# UI_Controller_Damping_R.net
KiCad netlist of a schematic drawn in EAGLE
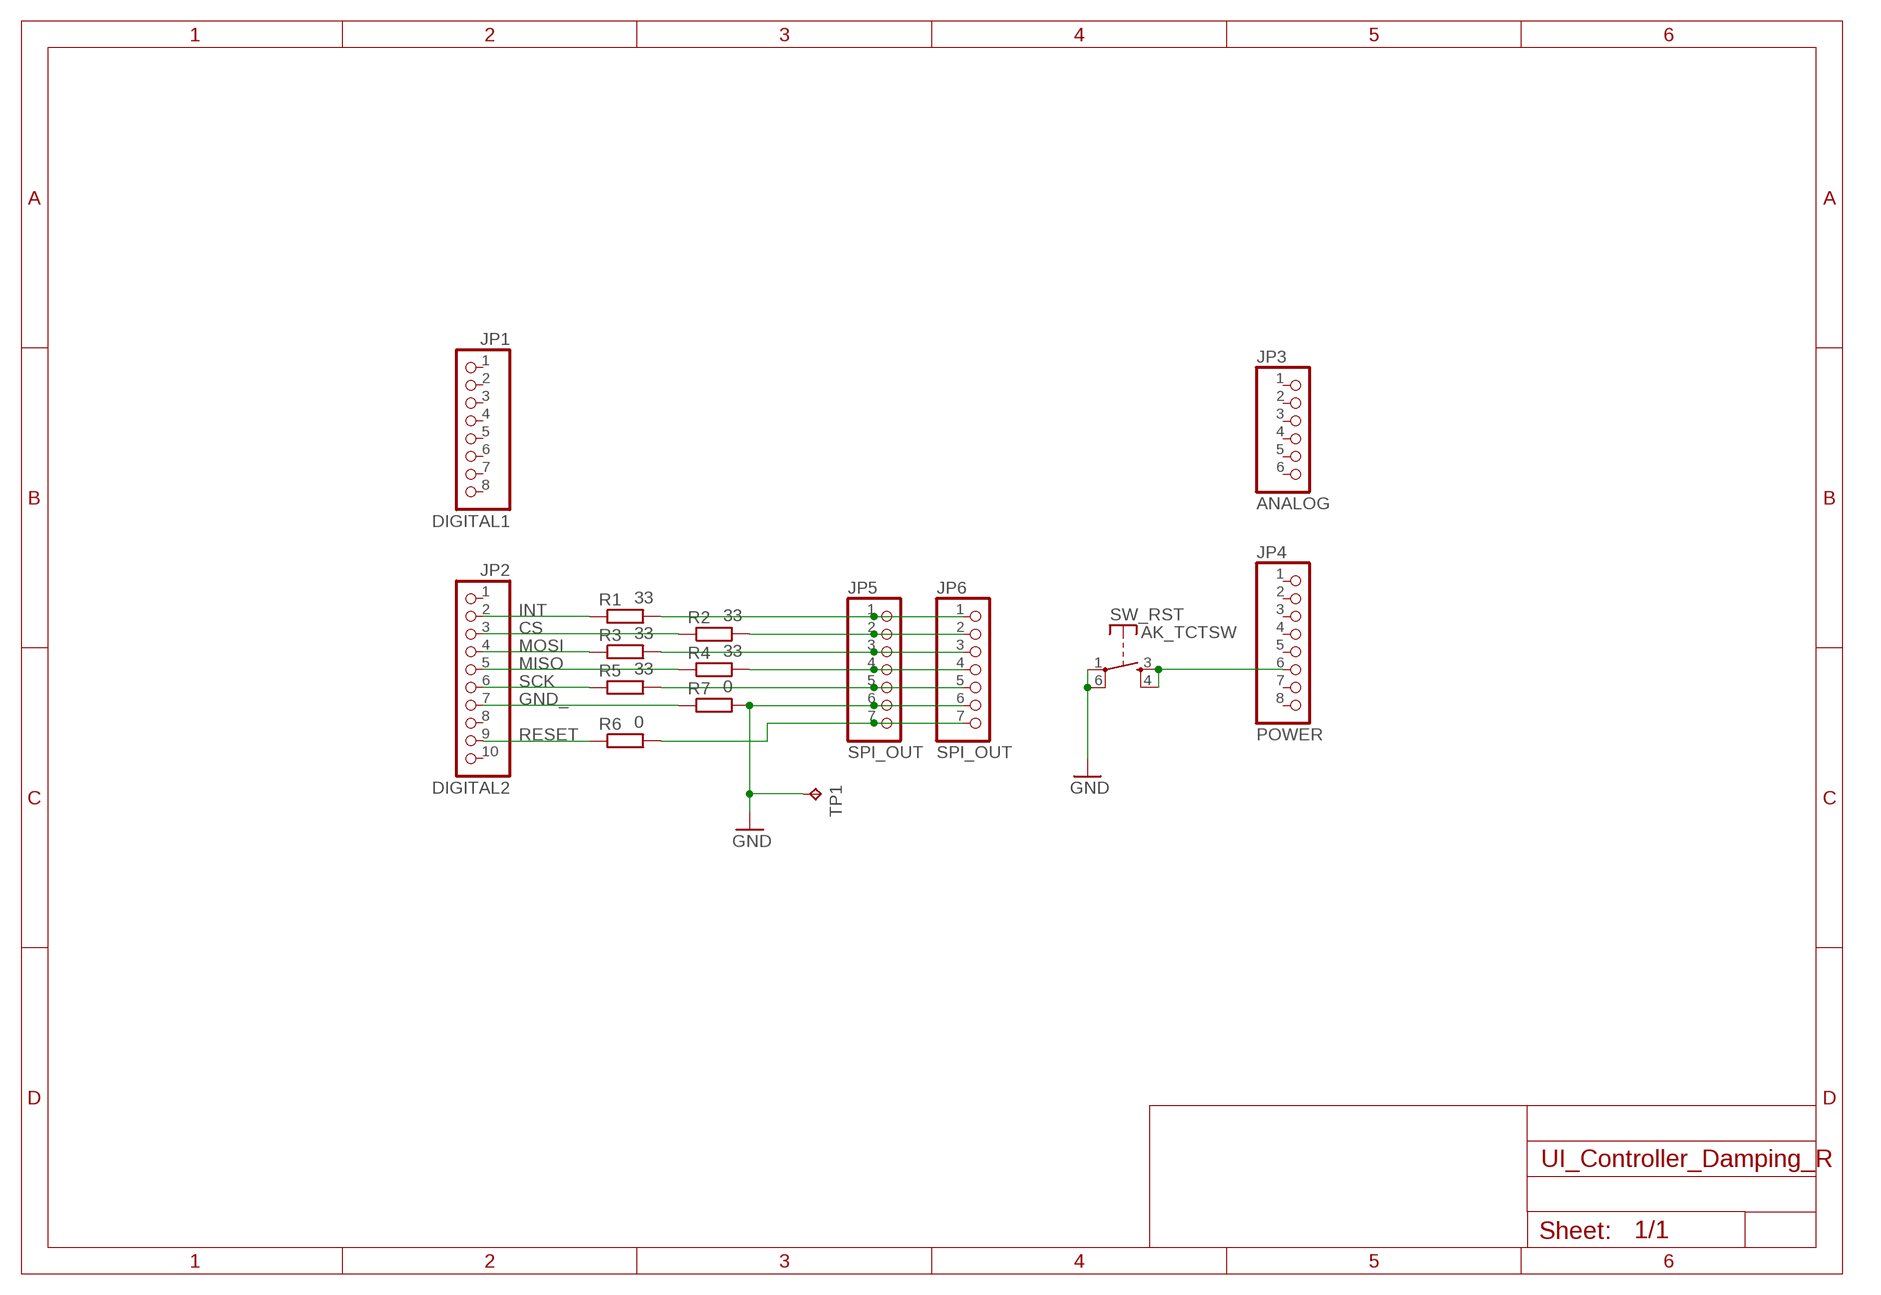
[diagram p0: schematic, sheet 1]

(export (version "E")
  (design (tool "Eeschema 10.0.6"))
  (components
    (comp (ref "JP1")
      (value "DIGITAL1")
      (footprint "eagle-import:1X08")
      (libsource (lib "eagle-import") (part "PINHD-1X8"))
    )
    (comp (ref "JP2")
      (value "DIGITAL2")
      (footprint "eagle-import:1X10")
      (libsource (lib "eagle-import") (part "PINHD-1X10"))
    )
    (comp (ref "JP3")
      (value "ANALOG")
      (footprint "eagle-import:1X06")
      (libsource (lib "eagle-import") (part "PINHD-1X6"))
    )
    (comp (ref "JP4")
      (value "POWER")
      (footprint "eagle-import:1X08")
      (libsource (lib "eagle-import") (part "PINHD-1X8"))
    )
    (comp (ref "JP5")
      (value "SPI_OUT")
      (footprint "eagle-import:1X07")
      (libsource (lib "eagle-import") (part "PINHD-1X7"))
    )
    (comp (ref "JP6")
      (value "SPI_OUT")
      (footprint "eagle-import:1X07")
      (libsource (lib "eagle-import") (part "PINHD-1X7"))
    )
    (comp (ref "R1")
      (value "33")
      (footprint "eagle-import:0207_7")
      (libsource (lib "eagle-import") (part "R-EU_0207/7"))
    )
    (comp (ref "R2")
      (value "33")
      (footprint "eagle-import:0207_7")
      (libsource (lib "eagle-import") (part "R-EU_0207/7"))
    )
    (comp (ref "R3")
      (value "33")
      (footprint "eagle-import:0207_7")
      (libsource (lib "eagle-import") (part "R-EU_0207/7"))
    )
    (comp (ref "R4")
      (value "33")
      (footprint "eagle-import:0207_7")
      (libsource (lib "eagle-import") (part "R-EU_0207/7"))
    )
    (comp (ref "R5")
      (value "33")
      (footprint "eagle-import:0207_7")
      (libsource (lib "eagle-import") (part "R-EU_0207/7"))
    )
    (comp (ref "R6")
      (value "0")
      (footprint "eagle-import:0207_7")
      (libsource (lib "eagle-import") (part "R-EU_0207/7"))
    )
    (comp (ref "R7")
      (value "0")
      (footprint "eagle-import:0207_7")
      (libsource (lib "eagle-import") (part "R-EU_0207/7"))
    )
    (comp (ref "SW_RST")
      (value "AK_TCTSW")
      (footprint "eagle-import:TME1")
      (libsource (lib "eagle-import") (part "AK_TCTSW"))
    )
    (comp (ref "TP1")
      (value "TPPAD1-13")
      (footprint "eagle-import:P1-13")
      (libsource (lib "eagle-import") (part "TPPAD1-13"))
    )
  )
  (nets
    (net (code "1") (name "/CS") (class "Default")
      (node (ref "JP2") (pin "3") (pinfunction "3_3") (pintype "passive"))
      (node (ref "R2") (pin "1") (pinfunction "1_1") (pintype "passive"))
    )
    (net (code "2") (name "/GND_") (class "Default")
      (node (ref "JP2") (pin "7") (pinfunction "7_7") (pintype "passive"))
      (node (ref "R7") (pin "1") (pinfunction "1_1") (pintype "passive"))
    )
    (net (code "3") (name "/INT") (class "Default")
      (node (ref "JP2") (pin "2") (pinfunction "2_2") (pintype "passive"))
      (node (ref "R1") (pin "1") (pinfunction "1_1") (pintype "passive"))
    )
    (net (code "4") (name "/MISO") (class "Default")
      (node (ref "JP2") (pin "5") (pinfunction "5_5") (pintype "passive"))
      (node (ref "R4") (pin "1") (pinfunction "1_1") (pintype "passive"))
    )
    (net (code "5") (name "/MOSI") (class "Default")
      (node (ref "JP2") (pin "4") (pinfunction "4_4") (pintype "passive"))
      (node (ref "R3") (pin "1") (pinfunction "1_1") (pintype "passive"))
    )
    (net (code "6") (name "/RESET") (class "Default")
      (node (ref "JP2") (pin "9") (pinfunction "9_9") (pintype "passive"))
      (node (ref "R6") (pin "1") (pinfunction "1_1") (pintype "passive"))
    )
    (net (code "7") (name "/SCK") (class "Default")
      (node (ref "JP2") (pin "6") (pinfunction "6_6") (pintype "passive"))
      (node (ref "R5") (pin "1") (pinfunction "1_1") (pintype "passive"))
    )
    (net (code "8") (name "GND") (class "Default")
      (node (ref "JP5") (pin "6") (pinfunction "6_6") (pintype "passive"))
      (node (ref "JP6") (pin "6") (pinfunction "6_6") (pintype "passive"))
      (node (ref "R7") (pin "2") (pinfunction "2_2") (pintype "passive"))
      (node (ref "SW_RST") (pin "1") (pinfunction "P_1") (pintype "passive"))
      (node (ref "SW_RST") (pin "6") (pinfunction "P_6") (pintype "passive"))
      (node (ref "TP1") (pin "TP") (pinfunction "TP_TP") (pintype "input"))
    )
    (net (code "9") (name "Net-(JP4-Pad6)") (class "Default")
      (node (ref "JP4") (pin "6") (pinfunction "6_6") (pintype "passive"))
      (node (ref "SW_RST") (pin "3") (pinfunction "S_3") (pintype "passive"))
      (node (ref "SW_RST") (pin "4") (pinfunction "S_4") (pintype "passive"))
    )
    (net (code "10") (name "Net-(JP5-Pad1)") (class "Default")
      (node (ref "JP5") (pin "1") (pinfunction "1_1") (pintype "passive"))
      (node (ref "JP6") (pin "1") (pinfunction "1_1") (pintype "passive"))
      (node (ref "R1") (pin "2") (pinfunction "2_2") (pintype "passive"))
    )
    (net (code "11") (name "Net-(JP5-Pad2)") (class "Default")
      (node (ref "JP5") (pin "2") (pinfunction "2_2") (pintype "passive"))
      (node (ref "JP6") (pin "2") (pinfunction "2_2") (pintype "passive"))
      (node (ref "R2") (pin "2") (pinfunction "2_2") (pintype "passive"))
    )
    (net (code "12") (name "Net-(JP5-Pad3)") (class "Default")
      (node (ref "JP5") (pin "3") (pinfunction "3_3") (pintype "passive"))
      (node (ref "JP6") (pin "3") (pinfunction "3_3") (pintype "passive"))
      (node (ref "R3") (pin "2") (pinfunction "2_2") (pintype "passive"))
    )
    (net (code "13") (name "Net-(JP5-Pad4)") (class "Default")
      (node (ref "JP5") (pin "4") (pinfunction "4_4") (pintype "passive"))
      (node (ref "JP6") (pin "4") (pinfunction "4_4") (pintype "passive"))
      (node (ref "R4") (pin "2") (pinfunction "2_2") (pintype "passive"))
    )
    (net (code "14") (name "Net-(JP5-Pad5)") (class "Default")
      (node (ref "JP5") (pin "5") (pinfunction "5_5") (pintype "passive"))
      (node (ref "JP6") (pin "5") (pinfunction "5_5") (pintype "passive"))
      (node (ref "R5") (pin "2") (pinfunction "2_2") (pintype "passive"))
    )
    (net (code "15") (name "Net-(JP5-Pad7)") (class "Default")
      (node (ref "JP5") (pin "7") (pinfunction "7_7") (pintype "passive"))
      (node (ref "JP6") (pin "7") (pinfunction "7_7") (pintype "passive"))
      (node (ref "R6") (pin "2") (pinfunction "2_2") (pintype "passive"))
    )
    (net (code "16") (name "unconnected-(JP1-Pad1)") (class "Default")
      (node (ref "JP1") (pin "1") (pinfunction "1_1") (pintype "passive"))
    )
    (net (code "17") (name "unconnected-(JP1-Pad2)") (class "Default")
      (node (ref "JP1") (pin "2") (pinfunction "2_2") (pintype "passive"))
    )
    (net (code "18") (name "unconnected-(JP1-Pad3)") (class "Default")
      (node (ref "JP1") (pin "3") (pinfunction "3_3") (pintype "passive"))
    )
    (net (code "19") (name "unconnected-(JP1-Pad4)") (class "Default")
      (node (ref "JP1") (pin "4") (pinfunction "4_4") (pintype "passive"))
    )
    (net (code "20") (name "unconnected-(JP1-Pad5)") (class "Default")
      (node (ref "JP1") (pin "5") (pinfunction "5_5") (pintype "passive"))
    )
    (net (code "21") (name "unconnected-(JP1-Pad6)") (class "Default")
      (node (ref "JP1") (pin "6") (pinfunction "6_6") (pintype "passive"))
    )
    (net (code "22") (name "unconnected-(JP1-Pad7)") (class "Default")
      (node (ref "JP1") (pin "7") (pinfunction "7_7") (pintype "passive"))
    )
    (net (code "23") (name "unconnected-(JP1-Pad8)") (class "Default")
      (node (ref "JP1") (pin "8") (pinfunction "8_8") (pintype "passive"))
    )
    (net (code "24") (name "unconnected-(JP2-Pad1)") (class "Default")
      (node (ref "JP2") (pin "1") (pinfunction "1_1") (pintype "passive"))
    )
    (net (code "25") (name "unconnected-(JP2-Pad8)") (class "Default")
      (node (ref "JP2") (pin "8") (pinfunction "8_8") (pintype "passive"))
    )
    (net (code "26") (name "unconnected-(JP2-Pad10)") (class "Default")
      (node (ref "JP2") (pin "10") (pinfunction "10_10") (pintype "passive"))
    )
    (net (code "27") (name "unconnected-(JP3-Pad1)") (class "Default")
      (node (ref "JP3") (pin "1") (pinfunction "1_1") (pintype "passive"))
    )
    (net (code "28") (name "unconnected-(JP3-Pad2)") (class "Default")
      (node (ref "JP3") (pin "2") (pinfunction "2_2") (pintype "passive"))
    )
    (net (code "29") (name "unconnected-(JP3-Pad3)") (class "Default")
      (node (ref "JP3") (pin "3") (pinfunction "3_3") (pintype "passive"))
    )
    (net (code "30") (name "unconnected-(JP3-Pad4)") (class "Default")
      (node (ref "JP3") (pin "4") (pinfunction "4_4") (pintype "passive"))
    )
    (net (code "31") (name "unconnected-(JP3-Pad5)") (class "Default")
      (node (ref "JP3") (pin "5") (pinfunction "5_5") (pintype "passive"))
    )
    (net (code "32") (name "unconnected-(JP3-Pad6)") (class "Default")
      (node (ref "JP3") (pin "6") (pinfunction "6_6") (pintype "passive"))
    )
    (net (code "33") (name "unconnected-(JP4-Pad1)") (class "Default")
      (node (ref "JP4") (pin "1") (pinfunction "1_1") (pintype "passive"))
    )
    (net (code "34") (name "unconnected-(JP4-Pad2)") (class "Default")
      (node (ref "JP4") (pin "2") (pinfunction "2_2") (pintype "passive"))
    )
    (net (code "35") (name "unconnected-(JP4-Pad3)") (class "Default")
      (node (ref "JP4") (pin "3") (pinfunction "3_3") (pintype "passive"))
    )
    (net (code "36") (name "unconnected-(JP4-Pad4)") (class "Default")
      (node (ref "JP4") (pin "4") (pinfunction "4_4") (pintype "passive"))
    )
    (net (code "37") (name "unconnected-(JP4-Pad5)") (class "Default")
      (node (ref "JP4") (pin "5") (pinfunction "5_5") (pintype "passive"))
    )
    (net (code "38") (name "unconnected-(JP4-Pad7)") (class "Default")
      (node (ref "JP4") (pin "7") (pinfunction "7_7") (pintype "passive"))
    )
    (net (code "39") (name "unconnected-(JP4-Pad8)") (class "Default")
      (node (ref "JP4") (pin "8") (pinfunction "8_8") (pintype "passive"))
    )
  )
)
